# IFX_breakout_04_eagle7.net
KiCad netlist of a schematic drawn in EAGLE
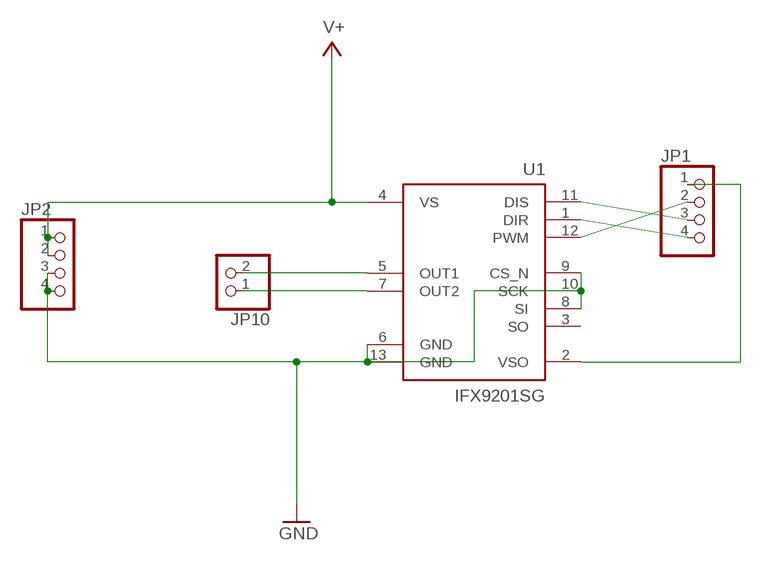
[diagram p0: schematic, sheet 1]

(export (version "E")
  (design (tool "Eeschema 10.0.6"))
  (components
    (comp (ref "JP1")
      (value "PINHD-1X4")
      (footprint "eagle-import:1X04")
      (libsource (lib "eagle-import") (part "PINHD-1X4"))
    )
    (comp (ref "JP2")
      (value "PINHD-1X4")
      (footprint "eagle-import:1X04")
      (libsource (lib "eagle-import") (part "PINHD-1X4"))
    )
    (comp (ref "JP10")
      (value "PINHD-1X2/90")
      (footprint "eagle-import:1X02_90")
      (libsource (lib "eagle-import") (part "PINHD-1X2/90"))
    )
    (comp (ref "U1")
      (value "IFX9201SG")
      (footprint "eagle-import:SOP100P1030X260-13N")
      (libsource (lib "eagle-import") (part "IFX9201SG"))
    )
  )
  (nets
    (net (code "1") (name "GND") (class "Default")
      (node (ref "JP2") (pin "3") (pinfunction "3_3") (pintype "passive"))
      (node (ref "JP2") (pin "4") (pinfunction "4_4") (pintype "passive"))
      (node (ref "U1") (pin "10") (pinfunction "SCK_10") (pintype "input"))
      (node (ref "U1") (pin "13") (pinfunction "GND_13") (pintype "power_in"))
      (node (ref "U1") (pin "6") (pinfunction "GND_6") (pintype "power_in"))
      (node (ref "U1") (pin "8") (pinfunction "SI_8") (pintype "input"))
      (node (ref "U1") (pin "9") (pinfunction "CS_N_9") (pintype "input"))
    )
    (net (code "2") (name "Net-(U1-DIR)") (class "Default")
      (node (ref "JP1") (pin "4") (pinfunction "4_4") (pintype "passive"))
      (node (ref "U1") (pin "1") (pinfunction "DIR_1") (pintype "input"))
    )
    (net (code "3") (name "Net-(U1-DIS)") (class "Default")
      (node (ref "JP1") (pin "3") (pinfunction "3_3") (pintype "passive"))
      (node (ref "U1") (pin "11") (pinfunction "DIS_11") (pintype "input"))
    )
    (net (code "4") (name "Net-(U1-OUT1)") (class "Default")
      (node (ref "JP10") (pin "2") (pinfunction "2_2") (pintype "passive"))
      (node (ref "U1") (pin "5") (pinfunction "OUT1_5") (pintype "output"))
    )
    (net (code "5") (name "Net-(U1-OUT2)") (class "Default")
      (node (ref "JP10") (pin "1") (pinfunction "1_1") (pintype "passive"))
      (node (ref "U1") (pin "7") (pinfunction "OUT2_7") (pintype "output"))
    )
    (net (code "6") (name "Net-(U1-PWM)") (class "Default")
      (node (ref "JP1") (pin "2") (pinfunction "2_2") (pintype "passive"))
      (node (ref "U1") (pin "12") (pinfunction "PWM_12") (pintype "input"))
    )
    (net (code "7") (name "Net-(U1-VSO)") (class "Default")
      (node (ref "JP1") (pin "1") (pinfunction "1_1") (pintype "passive"))
      (node (ref "U1") (pin "2") (pinfunction "VSO_2") (pintype "power_in"))
    )
    (net (code "8") (name "V+") (class "Default")
      (node (ref "JP2") (pin "1") (pinfunction "1_1") (pintype "passive"))
      (node (ref "JP2") (pin "2") (pinfunction "2_2") (pintype "passive"))
      (node (ref "U1") (pin "4") (pinfunction "VS_4") (pintype "power_in"))
    )
    (net (code "9") (name "unconnected-(U1-SO-Pad3)") (class "Default")
      (node (ref "U1") (pin "3") (pinfunction "SO_3") (pintype "output"))
    )
  )
)
